# Sensor_ExpandBoard_DS18B20.net
KiCad netlist of a schematic drawn in Altium Designer
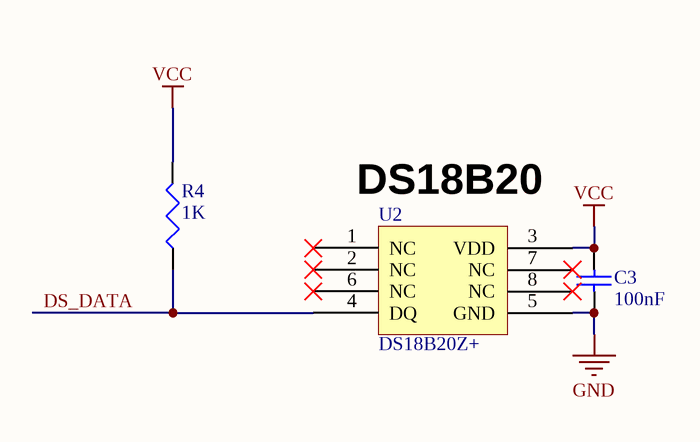
[diagram p0: Sensor_ExpandBoard_DS18B20.SchDoc]

(export (version "E")
  (design (tool "Eeschema 10.0.6"))
  (components
    (comp (ref "C3")
      (value "100nF")
      (footprint "0603-2")
      (description "无极性电容")
      (fields (field (name "PUBLISHER") "Altium Limited"))
      (libsource (lib "Fszhang") (part "Cap"))
    )
    (comp (ref "R4")
      (value "1K")
      (footprint "R0603")
      (description "Resistor")
      (fields (field (name "PUBLISHER") "Altium Limited"))
      (libsource (lib "step") (part "Res"))
    )
    (comp (ref "U2")
      (value "DS18B20Z+")
      (footprint "SOIC8_N")
      (description "温度传感器")
      (libsource (lib "Sensor") (part "DS18B20_SOP8"))
    )
  )
  (nets
    (net (code "1") (name "/DS_DATA") (class "Default")
      (node (ref "R4") (pin "1") (pinfunction "1_1") (pintype "passive"))
      (node (ref "U2") (pin "4") (pinfunction "DQ_4") (pintype "passive"))
    )
    (net (code "2") (name "GND") (class "Default")
      (node (ref "C3") (pin "1") (pinfunction "1_1") (pintype "passive"))
      (node (ref "U2") (pin "5") (pinfunction "GND_5") (pintype "passive"))
    )
    (net (code "3") (name "VCC") (class "Default")
      (node (ref "C3") (pin "2") (pinfunction "2_2") (pintype "passive"))
      (node (ref "R4") (pin "2") (pinfunction "2_2") (pintype "passive"))
      (node (ref "U2") (pin "3") (pinfunction "VDD_3") (pintype "passive"))
    )
    (net (code "4") (name "unconnected-(U2-NC-Pad1)") (class "Default")
      (node (ref "U2") (pin "1") (pinfunction "NC_1") (pintype "passive+no_connect"))
    )
    (net (code "5") (name "unconnected-(U2-NC-Pad2)") (class "Default")
      (node (ref "U2") (pin "2") (pinfunction "NC_2") (pintype "passive+no_connect"))
    )
    (net (code "6") (name "unconnected-(U2-NC-Pad6)") (class "Default")
      (node (ref "U2") (pin "6") (pinfunction "NC_6") (pintype "passive+no_connect"))
    )
    (net (code "7") (name "unconnected-(U2-NC-Pad7)") (class "Default")
      (node (ref "U2") (pin "7") (pinfunction "NC_7") (pintype "passive+no_connect"))
    )
    (net (code "8") (name "unconnected-(U2-NC-Pad8)") (class "Default")
      (node (ref "U2") (pin "8") (pinfunction "NC_8") (pintype "passive+no_connect"))
    )
  )
)
